# digitalclock2.net
KiCad netlist of a schematic drawn in EAGLE
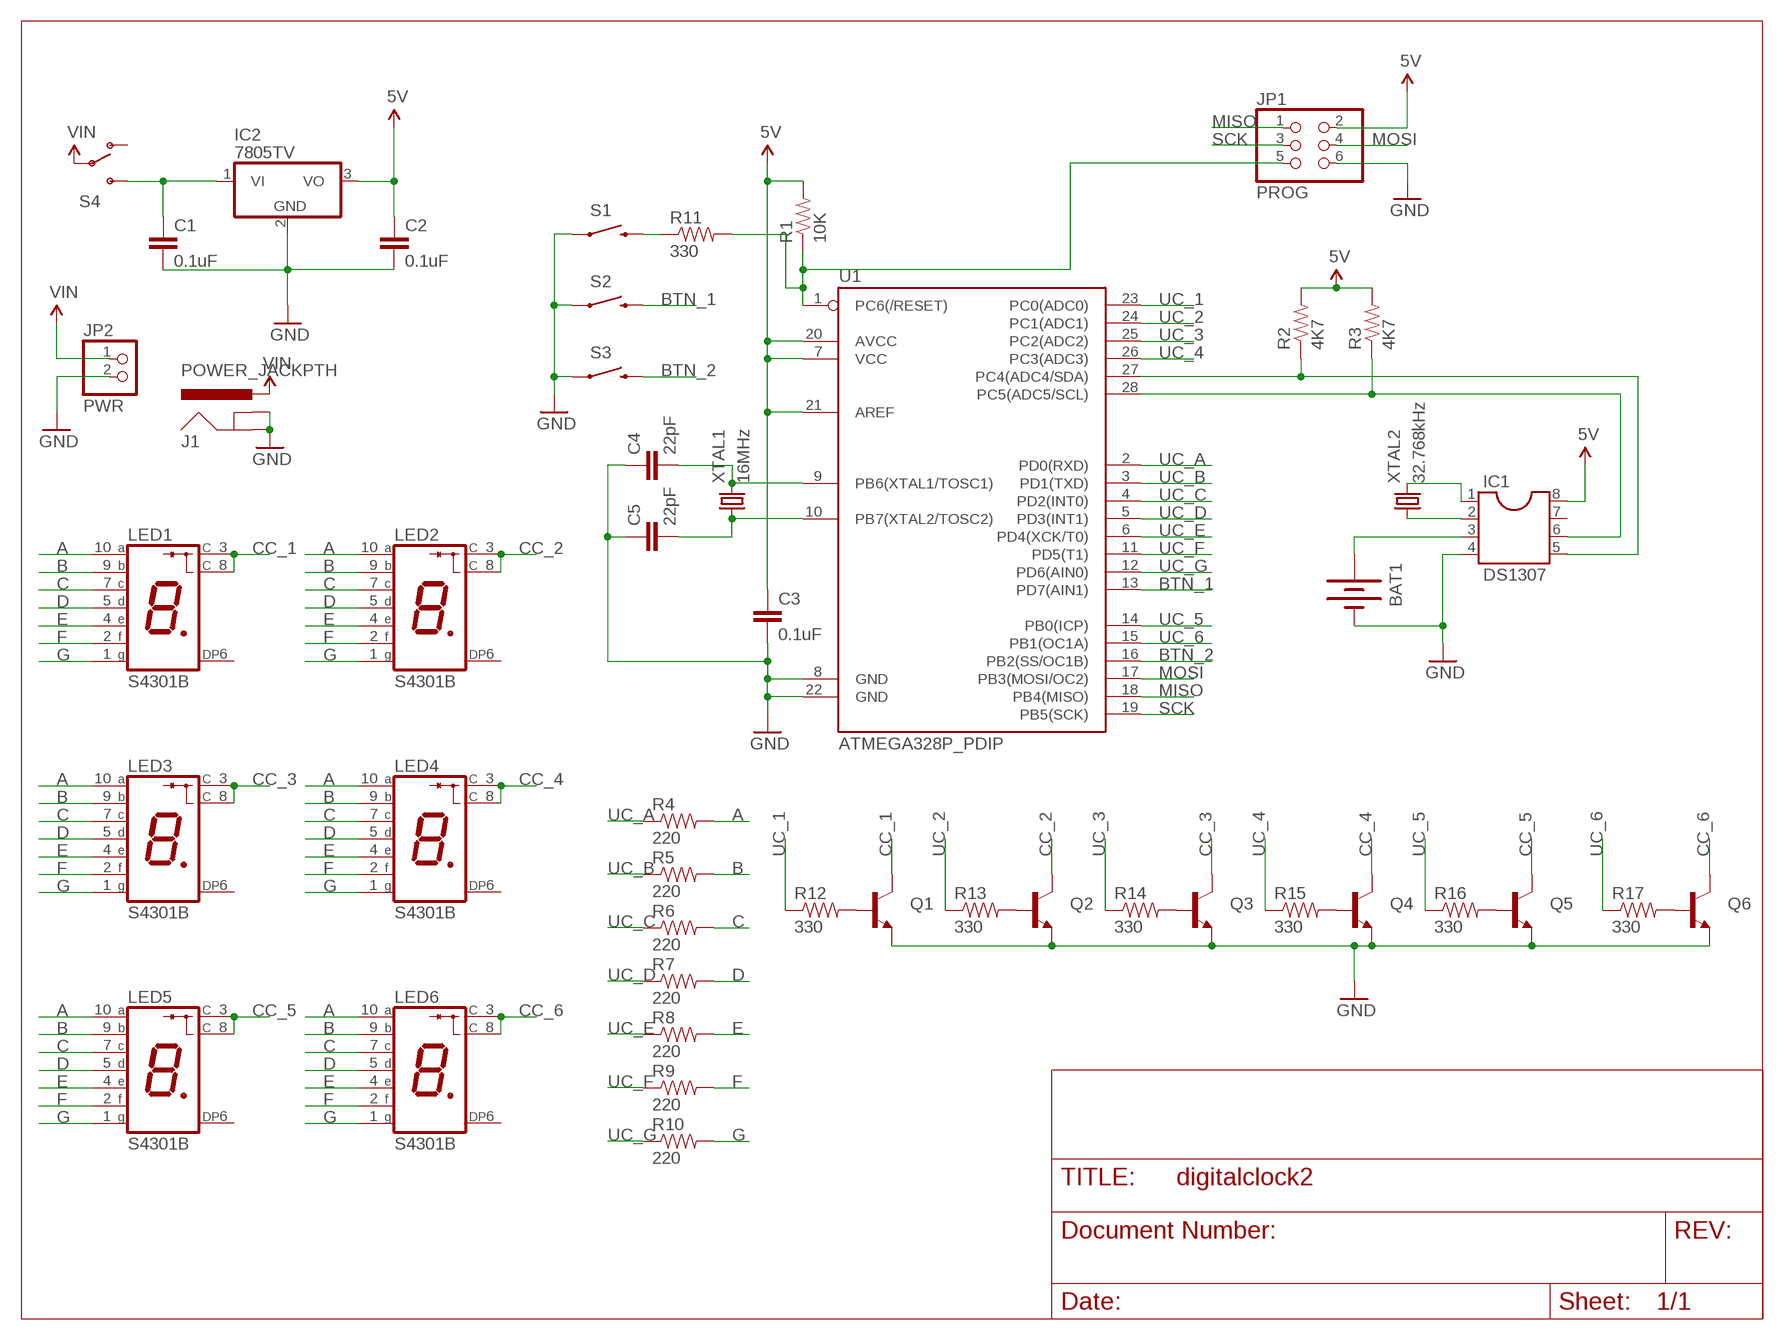
[diagram p0: schematic, sheet 1]

(export (version "E")
  (design (tool "Eeschema 10.0.6"))
  (components
    (comp (ref "BAT1")
      (value "BATTERY20PTH")
      (footprint "eagle-import:BATTCOM_20MM_PTH")
      (libsource (lib "eagle-import") (part "BATTERY20PTH"))
    )
    (comp (ref "C1")
      (value "0.1uF")
      (footprint "eagle-import:CAP-PTH-SMALL")
      (libsource (lib "eagle-import") (part "CAPPTH"))
    )
    (comp (ref "C2")
      (value "0.1uF")
      (footprint "eagle-import:CAP-PTH-SMALL")
      (libsource (lib "eagle-import") (part "CAPPTH"))
    )
    (comp (ref "C3")
      (value "0.1uF")
      (footprint "eagle-import:CAP-PTH-SMALL")
      (libsource (lib "eagle-import") (part "CAPPTH"))
    )
    (comp (ref "C4")
      (value "22pF")
      (footprint "eagle-import:CAP-PTH-SMALL")
      (libsource (lib "eagle-import") (part "CAPPTH"))
    )
    (comp (ref "C5")
      (value "22pF")
      (footprint "eagle-import:CAP-PTH-SMALL")
      (libsource (lib "eagle-import") (part "CAPPTH"))
    )
    (comp (ref "IC1")
      (value "DS1307")
      (footprint "eagle-import:SOCKET-08")
      (libsource (lib "eagle-import") (part "DIL8S"))
    )
    (comp (ref "IC2")
      (value "7805TV")
      (footprint "eagle-import:TO220V")
      (libsource (lib "eagle-import") (part "78TV05"))
    )
    (comp (ref "J1")
      (value "POWER_JACKPTH")
      (footprint "eagle-import:POWER_JACK_PTH")
      (libsource (lib "eagle-import") (part "POWER_JACKPTH"))
    )
    (comp (ref "JP1")
      (value "PROG")
      (footprint "eagle-import:2X03")
      (libsource (lib "eagle-import") (part "PINHD-2X3"))
    )
    (comp (ref "JP2")
      (value "PWR")
      (footprint "eagle-import:1X02")
      (libsource (lib "eagle-import") (part "PINHD-1X2"))
    )
    (comp (ref "LED1")
      (value "S4301B")
      (footprint "eagle-import:S4301B")
      (libsource (lib "eagle-import") (part "S4301B"))
    )
    (comp (ref "LED2")
      (value "S4301B")
      (footprint "eagle-import:S4301B")
      (libsource (lib "eagle-import") (part "S4301B"))
    )
    (comp (ref "LED3")
      (value "S4301B")
      (footprint "eagle-import:S4301B")
      (libsource (lib "eagle-import") (part "S4301B"))
    )
    (comp (ref "LED4")
      (value "S4301B")
      (footprint "eagle-import:S4301B")
      (libsource (lib "eagle-import") (part "S4301B"))
    )
    (comp (ref "LED5")
      (value "S4301B")
      (footprint "eagle-import:S4301B")
      (libsource (lib "eagle-import") (part "S4301B"))
    )
    (comp (ref "LED6")
      (value "S4301B")
      (footprint "eagle-import:S4301B")
      (libsource (lib "eagle-import") (part "S4301B"))
    )
    (comp (ref "Q1")
      (value "TRANSISTOR_NPNTO-92-AMMO")
      (footprint "eagle-import:TO-92-AMMO")
      (libsource (lib "eagle-import") (part "TRANSISTOR_NPNTO-92-AMMO"))
    )
    (comp (ref "Q2")
      (value "TRANSISTOR_NPNTO-92-AMMO")
      (footprint "eagle-import:TO-92-AMMO")
      (libsource (lib "eagle-import") (part "TRANSISTOR_NPNTO-92-AMMO"))
    )
    (comp (ref "Q3")
      (value "TRANSISTOR_NPNTO-92-AMMO")
      (footprint "eagle-import:TO-92-AMMO")
      (libsource (lib "eagle-import") (part "TRANSISTOR_NPNTO-92-AMMO"))
    )
    (comp (ref "Q4")
      (value "TRANSISTOR_NPNTO-92-AMMO")
      (footprint "eagle-import:TO-92-AMMO")
      (libsource (lib "eagle-import") (part "TRANSISTOR_NPNTO-92-AMMO"))
    )
    (comp (ref "Q5")
      (value "TRANSISTOR_NPNTO-92-AMMO")
      (footprint "eagle-import:TO-92-AMMO")
      (libsource (lib "eagle-import") (part "TRANSISTOR_NPNTO-92-AMMO"))
    )
    (comp (ref "Q6")
      (value "TRANSISTOR_NPNTO-92-AMMO")
      (footprint "eagle-import:TO-92-AMMO")
      (libsource (lib "eagle-import") (part "TRANSISTOR_NPNTO-92-AMMO"))
    )
    (comp (ref "R1")
      (value "10K")
      (footprint "eagle-import:AXIAL-0.3")
      (libsource (lib "eagle-import") (part "RESISTORAXIAL-0.3"))
    )
    (comp (ref "R2")
      (value "4K7")
      (footprint "eagle-import:AXIAL-0.3")
      (libsource (lib "eagle-import") (part "RESISTORAXIAL-0.3"))
    )
    (comp (ref "R3")
      (value "4K7")
      (footprint "eagle-import:AXIAL-0.3")
      (libsource (lib "eagle-import") (part "RESISTORAXIAL-0.3"))
    )
    (comp (ref "R4")
      (value "220")
      (footprint "eagle-import:AXIAL-0.3")
      (libsource (lib "eagle-import") (part "RESISTORAXIAL-0.3"))
    )
    (comp (ref "R5")
      (value "220")
      (footprint "eagle-import:AXIAL-0.3")
      (libsource (lib "eagle-import") (part "RESISTORAXIAL-0.3"))
    )
    (comp (ref "R6")
      (value "220")
      (footprint "eagle-import:AXIAL-0.3")
      (libsource (lib "eagle-import") (part "RESISTORAXIAL-0.3"))
    )
    (comp (ref "R7")
      (value "220")
      (footprint "eagle-import:AXIAL-0.3")
      (libsource (lib "eagle-import") (part "RESISTORAXIAL-0.3"))
    )
    (comp (ref "R8")
      (value "220")
      (footprint "eagle-import:AXIAL-0.3")
      (libsource (lib "eagle-import") (part "RESISTORAXIAL-0.3"))
    )
    (comp (ref "R9")
      (value "220")
      (footprint "eagle-import:AXIAL-0.3")
      (libsource (lib "eagle-import") (part "RESISTORAXIAL-0.3"))
    )
    (comp (ref "R10")
      (value "220")
      (footprint "eagle-import:AXIAL-0.3")
      (libsource (lib "eagle-import") (part "RESISTORAXIAL-0.3"))
    )
    (comp (ref "R11")
      (value "330")
      (footprint "eagle-import:AXIAL-0.3")
      (libsource (lib "eagle-import") (part "RESISTORAXIAL-0.3"))
    )
    (comp (ref "R12")
      (value "330")
      (footprint "eagle-import:AXIAL-0.3")
      (libsource (lib "eagle-import") (part "RESISTORAXIAL-0.3"))
    )
    (comp (ref "R13")
      (value "330")
      (footprint "eagle-import:AXIAL-0.3")
      (libsource (lib "eagle-import") (part "RESISTORAXIAL-0.3"))
    )
    (comp (ref "R14")
      (value "330")
      (footprint "eagle-import:AXIAL-0.3")
      (libsource (lib "eagle-import") (part "RESISTORAXIAL-0.3"))
    )
    (comp (ref "R15")
      (value "330")
      (footprint "eagle-import:AXIAL-0.3")
      (libsource (lib "eagle-import") (part "RESISTORAXIAL-0.3"))
    )
    (comp (ref "R16")
      (value "330")
      (footprint "eagle-import:AXIAL-0.3")
      (libsource (lib "eagle-import") (part "RESISTORAXIAL-0.3"))
    )
    (comp (ref "R17")
      (value "330")
      (footprint "eagle-import:AXIAL-0.3")
      (libsource (lib "eagle-import") (part "RESISTORAXIAL-0.3"))
    )
    (comp (ref "S1")
      (value "SWITCH-MOMENTARY-2PTH")
      (footprint "eagle-import:TACTILE-PTH")
      (libsource (lib "eagle-import") (part "SWITCH-MOMENTARY-2PTH"))
    )
    (comp (ref "S2")
      (value "SWITCH-MOMENTARY-2PTH")
      (footprint "eagle-import:TACTILE-PTH")
      (libsource (lib "eagle-import") (part "SWITCH-MOMENTARY-2PTH"))
    )
    (comp (ref "S3")
      (value "SWITCH-MOMENTARY-2PTH")
      (footprint "eagle-import:TACTILE-PTH")
      (libsource (lib "eagle-import") (part "SWITCH-MOMENTARY-2PTH"))
    )
    (comp (ref "S4")
      (value "SWITCH-SPDTPTH")
      (footprint "eagle-import:SWITCH-SPDT")
      (libsource (lib "eagle-import") (part "SWITCH-SPDTPTH"))
    )
    (comp (ref "U1")
      (value "ATMEGA328P_PDIP")
      (footprint "eagle-import:DIL28-3")
      (libsource (lib "eagle-import") (part "ATMEGA328P_PDIP"))
    )
    (comp (ref "XTAL1")
      (value "16MHz")
      (footprint "eagle-import:HC49_S")
      (libsource (lib "eagle-import") (part "CRYSTALHC49S"))
    )
    (comp (ref "XTAL2")
      (value "32.768kHz")
      (footprint "eagle-import:TC26V")
      (libsource (lib "eagle-import") (part "CRYSTALTC26V"))
    )
  )
  (nets
    (net (code "1") (name "/A") (class "Default")
      (node (ref "LED1") (pin "10") (pinfunction "A_10") (pintype "passive"))
      (node (ref "LED2") (pin "10") (pinfunction "A_10") (pintype "passive"))
      (node (ref "LED3") (pin "10") (pinfunction "A_10") (pintype "passive"))
      (node (ref "LED4") (pin "10") (pinfunction "A_10") (pintype "passive"))
      (node (ref "LED5") (pin "10") (pinfunction "A_10") (pintype "passive"))
      (node (ref "LED6") (pin "10") (pinfunction "A_10") (pintype "passive"))
      (node (ref "R4") (pin "P$2") (pinfunction "2_P$2") (pintype "passive"))
    )
    (net (code "2") (name "/B") (class "Default")
      (node (ref "LED1") (pin "9") (pinfunction "B_9") (pintype "passive"))
      (node (ref "LED2") (pin "9") (pinfunction "B_9") (pintype "passive"))
      (node (ref "LED3") (pin "9") (pinfunction "B_9") (pintype "passive"))
      (node (ref "LED4") (pin "9") (pinfunction "B_9") (pintype "passive"))
      (node (ref "LED5") (pin "9") (pinfunction "B_9") (pintype "passive"))
      (node (ref "LED6") (pin "9") (pinfunction "B_9") (pintype "passive"))
      (node (ref "R5") (pin "P$2") (pinfunction "2_P$2") (pintype "passive"))
    )
    (net (code "3") (name "/BTN_1") (class "Default")
      (node (ref "S2") (pin "3") (pinfunction "2_3") (pintype "passive"))
      (node (ref "U1") (pin "13") (pinfunction "PD7(AIN1)_13") (pintype "bidirectional"))
    )
    (net (code "4") (name "/BTN_2") (class "Default")
      (node (ref "S3") (pin "3") (pinfunction "2_3") (pintype "passive"))
      (node (ref "U1") (pin "16") (pinfunction "PB2(SS/OC1B)_16") (pintype "bidirectional"))
    )
    (net (code "5") (name "/C") (class "Default")
      (node (ref "LED1") (pin "7") (pinfunction "C_7") (pintype "passive"))
      (node (ref "LED2") (pin "7") (pinfunction "C_7") (pintype "passive"))
      (node (ref "LED3") (pin "7") (pinfunction "C_7") (pintype "passive"))
      (node (ref "LED4") (pin "7") (pinfunction "C_7") (pintype "passive"))
      (node (ref "LED5") (pin "7") (pinfunction "C_7") (pintype "passive"))
      (node (ref "LED6") (pin "7") (pinfunction "C_7") (pintype "passive"))
      (node (ref "R6") (pin "P$2") (pinfunction "2_P$2") (pintype "passive"))
    )
    (net (code "6") (name "/CC_1") (class "Default")
      (node (ref "LED1") (pin "3") (pinfunction "C_3") (pintype "passive"))
      (node (ref "LED1") (pin "8") (pinfunction "C_8") (pintype "passive"))
      (node (ref "Q1") (pin "3") (pinfunction "C_3") (pintype "passive"))
    )
    (net (code "7") (name "/CC_2") (class "Default")
      (node (ref "LED2") (pin "3") (pinfunction "C_3") (pintype "passive"))
      (node (ref "LED2") (pin "8") (pinfunction "C_8") (pintype "passive"))
      (node (ref "Q2") (pin "3") (pinfunction "C_3") (pintype "passive"))
    )
    (net (code "8") (name "/CC_3") (class "Default")
      (node (ref "LED3") (pin "3") (pinfunction "C_3") (pintype "passive"))
      (node (ref "LED3") (pin "8") (pinfunction "C_8") (pintype "passive"))
      (node (ref "Q3") (pin "3") (pinfunction "C_3") (pintype "passive"))
    )
    (net (code "9") (name "/CC_4") (class "Default")
      (node (ref "LED4") (pin "3") (pinfunction "C_3") (pintype "passive"))
      (node (ref "LED4") (pin "8") (pinfunction "C_8") (pintype "passive"))
      (node (ref "Q4") (pin "3") (pinfunction "C_3") (pintype "passive"))
    )
    (net (code "10") (name "/CC_5") (class "Default")
      (node (ref "LED5") (pin "3") (pinfunction "C_3") (pintype "passive"))
      (node (ref "LED5") (pin "8") (pinfunction "C_8") (pintype "passive"))
      (node (ref "Q5") (pin "3") (pinfunction "C_3") (pintype "passive"))
    )
    (net (code "11") (name "/CC_6") (class "Default")
      (node (ref "LED6") (pin "3") (pinfunction "C_3") (pintype "passive"))
      (node (ref "LED6") (pin "8") (pinfunction "C_8") (pintype "passive"))
      (node (ref "Q6") (pin "3") (pinfunction "C_3") (pintype "passive"))
    )
    (net (code "12") (name "/D") (class "Default")
      (node (ref "LED1") (pin "5") (pinfunction "D_5") (pintype "passive"))
      (node (ref "LED2") (pin "5") (pinfunction "D_5") (pintype "passive"))
      (node (ref "LED3") (pin "5") (pinfunction "D_5") (pintype "passive"))
      (node (ref "LED4") (pin "5") (pinfunction "D_5") (pintype "passive"))
      (node (ref "LED5") (pin "5") (pinfunction "D_5") (pintype "passive"))
      (node (ref "LED6") (pin "5") (pinfunction "D_5") (pintype "passive"))
      (node (ref "R7") (pin "P$2") (pinfunction "2_P$2") (pintype "passive"))
    )
    (net (code "13") (name "/E") (class "Default")
      (node (ref "LED1") (pin "4") (pinfunction "E_4") (pintype "passive"))
      (node (ref "LED2") (pin "4") (pinfunction "E_4") (pintype "passive"))
      (node (ref "LED3") (pin "4") (pinfunction "E_4") (pintype "passive"))
      (node (ref "LED4") (pin "4") (pinfunction "E_4") (pintype "passive"))
      (node (ref "LED5") (pin "4") (pinfunction "E_4") (pintype "passive"))
      (node (ref "LED6") (pin "4") (pinfunction "E_4") (pintype "passive"))
      (node (ref "R8") (pin "P$2") (pinfunction "2_P$2") (pintype "passive"))
    )
    (net (code "14") (name "/F") (class "Default")
      (node (ref "LED1") (pin "2") (pinfunction "F_2") (pintype "passive"))
      (node (ref "LED2") (pin "2") (pinfunction "F_2") (pintype "passive"))
      (node (ref "LED3") (pin "2") (pinfunction "F_2") (pintype "passive"))
      (node (ref "LED4") (pin "2") (pinfunction "F_2") (pintype "passive"))
      (node (ref "LED5") (pin "2") (pinfunction "F_2") (pintype "passive"))
      (node (ref "LED6") (pin "2") (pinfunction "F_2") (pintype "passive"))
      (node (ref "R9") (pin "P$2") (pinfunction "2_P$2") (pintype "passive"))
    )
    (net (code "15") (name "/G") (class "Default")
      (node (ref "LED1") (pin "1") (pinfunction "G_1") (pintype "passive"))
      (node (ref "LED2") (pin "1") (pinfunction "G_1") (pintype "passive"))
      (node (ref "LED3") (pin "1") (pinfunction "G_1") (pintype "passive"))
      (node (ref "LED4") (pin "1") (pinfunction "G_1") (pintype "passive"))
      (node (ref "LED5") (pin "1") (pinfunction "G_1") (pintype "passive"))
      (node (ref "LED6") (pin "1") (pinfunction "G_1") (pintype "passive"))
      (node (ref "R10") (pin "P$2") (pinfunction "2_P$2") (pintype "passive"))
    )
    (net (code "16") (name "/MISO") (class "Default")
      (node (ref "JP1") (pin "1") (pinfunction "1_1") (pintype "passive"))
      (node (ref "U1") (pin "18") (pinfunction "PB4(MISO)_18") (pintype "bidirectional"))
    )
    (net (code "17") (name "/MOSI") (class "Default")
      (node (ref "JP1") (pin "4") (pinfunction "4_4") (pintype "passive"))
      (node (ref "U1") (pin "17") (pinfunction "PB3(MOSI/OC2)_17") (pintype "bidirectional"))
    )
    (net (code "18") (name "/SCK") (class "Default")
      (node (ref "JP1") (pin "3") (pinfunction "3_3") (pintype "passive"))
      (node (ref "U1") (pin "19") (pinfunction "PB5(SCK)_19") (pintype "bidirectional"))
    )
    (net (code "19") (name "/UC_1") (class "Default")
      (node (ref "R12") (pin "P$1") (pinfunction "1_P$1") (pintype "passive"))
      (node (ref "U1") (pin "23") (pinfunction "PC0(ADC0)_23") (pintype "bidirectional"))
    )
    (net (code "20") (name "/UC_2") (class "Default")
      (node (ref "R13") (pin "P$1") (pinfunction "1_P$1") (pintype "passive"))
      (node (ref "U1") (pin "24") (pinfunction "PC1(ADC1)_24") (pintype "bidirectional"))
    )
    (net (code "21") (name "/UC_3") (class "Default")
      (node (ref "R14") (pin "P$1") (pinfunction "1_P$1") (pintype "passive"))
      (node (ref "U1") (pin "25") (pinfunction "PC2(ADC2)_25") (pintype "bidirectional"))
    )
    (net (code "22") (name "/UC_4") (class "Default")
      (node (ref "R15") (pin "P$1") (pinfunction "1_P$1") (pintype "passive"))
      (node (ref "U1") (pin "26") (pinfunction "PC3(ADC3)_26") (pintype "bidirectional"))
    )
    (net (code "23") (name "/UC_5") (class "Default")
      (node (ref "R16") (pin "P$1") (pinfunction "1_P$1") (pintype "passive"))
      (node (ref "U1") (pin "14") (pinfunction "PB0(ICP)_14") (pintype "bidirectional"))
    )
    (net (code "24") (name "/UC_6") (class "Default")
      (node (ref "R17") (pin "P$1") (pinfunction "1_P$1") (pintype "passive"))
      (node (ref "U1") (pin "15") (pinfunction "PB1(OC1A)_15") (pintype "bidirectional"))
    )
    (net (code "25") (name "/UC_A") (class "Default")
      (node (ref "R4") (pin "P$1") (pinfunction "1_P$1") (pintype "passive"))
      (node (ref "U1") (pin "2") (pinfunction "PD0(RXD)_2") (pintype "bidirectional"))
    )
    (net (code "26") (name "/UC_B") (class "Default")
      (node (ref "R5") (pin "P$1") (pinfunction "1_P$1") (pintype "passive"))
      (node (ref "U1") (pin "3") (pinfunction "PD1(TXD)_3") (pintype "bidirectional"))
    )
    (net (code "27") (name "/UC_C") (class "Default")
      (node (ref "R6") (pin "P$1") (pinfunction "1_P$1") (pintype "passive"))
      (node (ref "U1") (pin "4") (pinfunction "PD2(INT0)_4") (pintype "bidirectional"))
    )
    (net (code "28") (name "/UC_D") (class "Default")
      (node (ref "R7") (pin "P$1") (pinfunction "1_P$1") (pintype "passive"))
      (node (ref "U1") (pin "5") (pinfunction "PD3(INT1)_5") (pintype "bidirectional"))
    )
    (net (code "29") (name "/UC_E") (class "Default")
      (node (ref "R8") (pin "P$1") (pinfunction "1_P$1") (pintype "passive"))
      (node (ref "U1") (pin "6") (pinfunction "PD4(XCK/T0)_6") (pintype "bidirectional"))
    )
    (net (code "30") (name "/UC_F") (class "Default")
      (node (ref "R9") (pin "P$1") (pinfunction "1_P$1") (pintype "passive"))
      (node (ref "U1") (pin "11") (pinfunction "PD5(T1)_11") (pintype "bidirectional"))
    )
    (net (code "31") (name "/UC_G") (class "Default")
      (node (ref "R10") (pin "P$1") (pinfunction "1_P$1") (pintype "passive"))
      (node (ref "U1") (pin "12") (pinfunction "PD6(AIN0)_12") (pintype "bidirectional"))
    )
    (net (code "32") (name "5V") (class "Default")
      (node (ref "C2") (pin "1") (pinfunction "1_1") (pintype "passive"))
      (node (ref "C3") (pin "1") (pinfunction "1_1") (pintype "passive"))
      (node (ref "IC1") (pin "8") (pinfunction "8_8") (pintype "passive"))
      (node (ref "IC2") (pin "3") (pinfunction "VO_3") (pintype "passive"))
      (node (ref "JP1") (pin "2") (pinfunction "2_2") (pintype "passive"))
      (node (ref "R1") (pin "P$2") (pinfunction "2_P$2") (pintype "passive"))
      (node (ref "R2") (pin "P$2") (pinfunction "2_P$2") (pintype "passive"))
      (node (ref "R3") (pin "P$2") (pinfunction "2_P$2") (pintype "passive"))
      (node (ref "U1") (pin "20") (pinfunction "AVCC_20") (pintype "bidirectional"))
      (node (ref "U1") (pin "21") (pinfunction "AREF_21") (pintype "bidirectional"))
      (node (ref "U1") (pin "7") (pinfunction "VCC_7") (pintype "bidirectional"))
    )
    (net (code "33") (name "GND") (class "Default")
      (node (ref "BAT1") (pin "2") (pinfunction "-_2") (pintype "power_in"))
      (node (ref "C1") (pin "2") (pinfunction "2_2") (pintype "passive"))
      (node (ref "C2") (pin "2") (pinfunction "2_2") (pintype "passive"))
      (node (ref "C3") (pin "2") (pinfunction "2_2") (pintype "passive"))
      (node (ref "C4") (pin "1") (pinfunction "1_1") (pintype "passive"))
      (node (ref "C5") (pin "1") (pinfunction "1_1") (pintype "passive"))
      (node (ref "IC1") (pin "4") (pinfunction "4_4") (pintype "passive"))
      (node (ref "IC2") (pin "2") (pinfunction "GND_2") (pintype "passive"))
      (node (ref "J1") (pin "GND") (pinfunction "GND_GND") (pintype "bidirectional"))
      (node (ref "J1") (pin "GNDBREAK") (pinfunction "GNDBREAK_GNDBREAK") (pintype "bidirectional"))
      (node (ref "JP1") (pin "6") (pinfunction "6_6") (pintype "passive"))
      (node (ref "JP2") (pin "2") (pinfunction "2_2") (pintype "passive"))
      (node (ref "Q1") (pin "1") (pinfunction "E_1") (pintype "passive"))
      (node (ref "Q2") (pin "1") (pinfunction "E_1") (pintype "passive"))
      (node (ref "Q3") (pin "1") (pinfunction "E_1") (pintype "passive"))
      (node (ref "Q4") (pin "1") (pinfunction "E_1") (pintype "passive"))
      (node (ref "Q5") (pin "1") (pinfunction "E_1") (pintype "passive"))
      (node (ref "Q6") (pin "1") (pinfunction "E_1") (pintype "passive"))
      (node (ref "S1") (pin "1") (pinfunction "1_1") (pintype "passive"))
      (node (ref "S2") (pin "1") (pinfunction "1_1") (pintype "passive"))
      (node (ref "S3") (pin "1") (pinfunction "1_1") (pintype "passive"))
      (node (ref "U1") (pin "22") (pinfunction "GND_22") (pintype "bidirectional"))
      (node (ref "U1") (pin "8") (pinfunction "GND_8") (pintype "bidirectional"))
    )
    (net (code "34") (name "Net-(BAT1-+)") (class "Default")
      (node (ref "BAT1") (pin "1") (pinfunction "+_1") (pintype "power_in"))
      (node (ref "IC1") (pin "3") (pinfunction "3_3") (pintype "passive"))
    )
    (net (code "35") (name "Net-(IC1-Pad1)") (class "Default")
      (node (ref "IC1") (pin "1") (pinfunction "1_1") (pintype "passive"))
      (node (ref "XTAL2") (pin "2") (pinfunction "2_2") (pintype "passive"))
    )
    (net (code "36") (name "Net-(IC1-Pad2)") (class "Default")
      (node (ref "IC1") (pin "2") (pinfunction "2_2") (pintype "passive"))
      (node (ref "XTAL2") (pin "1") (pinfunction "1_1") (pintype "passive"))
    )
    (net (code "37") (name "Net-(IC2-VI)") (class "Default")
      (node (ref "C1") (pin "1") (pinfunction "1_1") (pintype "passive"))
      (node (ref "IC2") (pin "1") (pinfunction "VI_1") (pintype "input"))
      (node (ref "S4") (pin "3") (pinfunction "S_3") (pintype "passive"))
    )
    (net (code "38") (name "Net-(Q1-B)") (class "Default")
      (node (ref "Q1") (pin "2") (pinfunction "B_2") (pintype "passive"))
      (node (ref "R12") (pin "P$2") (pinfunction "2_P$2") (pintype "passive"))
    )
    (net (code "39") (name "Net-(Q2-B)") (class "Default")
      (node (ref "Q2") (pin "2") (pinfunction "B_2") (pintype "passive"))
      (node (ref "R13") (pin "P$2") (pinfunction "2_P$2") (pintype "passive"))
    )
    (net (code "40") (name "Net-(Q3-B)") (class "Default")
      (node (ref "Q3") (pin "2") (pinfunction "B_2") (pintype "passive"))
      (node (ref "R14") (pin "P$2") (pinfunction "2_P$2") (pintype "passive"))
    )
    (net (code "41") (name "Net-(Q4-B)") (class "Default")
      (node (ref "Q4") (pin "2") (pinfunction "B_2") (pintype "passive"))
      (node (ref "R15") (pin "P$2") (pinfunction "2_P$2") (pintype "passive"))
    )
    (net (code "42") (name "Net-(Q5-B)") (class "Default")
      (node (ref "Q5") (pin "2") (pinfunction "B_2") (pintype "passive"))
      (node (ref "R16") (pin "P$2") (pinfunction "2_P$2") (pintype "passive"))
    )
    (net (code "43") (name "Net-(Q6-B)") (class "Default")
      (node (ref "Q6") (pin "2") (pinfunction "B_2") (pintype "passive"))
      (node (ref "R17") (pin "P$2") (pinfunction "2_P$2") (pintype "passive"))
    )
    (net (code "44") (name "Net-(R1-1)") (class "Default")
      (node (ref "JP1") (pin "5") (pinfunction "5_5") (pintype "passive"))
      (node (ref "R1") (pin "P$1") (pinfunction "1_P$1") (pintype "passive"))
      (node (ref "R11") (pin "P$2") (pinfunction "2_P$2") (pintype "passive"))
      (node (ref "U1") (pin "1") (pinfunction "PC6(/RESET)_1") (pintype "bidirectional"))
    )
    (net (code "45") (name "Net-(R2-1)") (class "Default")
      (node (ref "IC1") (pin "5") (pinfunction "5_5") (pintype "passive"))
      (node (ref "R2") (pin "P$1") (pinfunction "1_P$1") (pintype "passive"))
      (node (ref "U1") (pin "27") (pinfunction "PC4(ADC4/SDA)_27") (pintype "bidirectional"))
    )
    (net (code "46") (name "Net-(R3-1)") (class "Default")
      (node (ref "IC1") (pin "6") (pinfunction "6_6") (pintype "passive"))
      (node (ref "R3") (pin "P$1") (pinfunction "1_P$1") (pintype "passive"))
      (node (ref "U1") (pin "28") (pinfunction "PC5(ADC5/SCL)_28") (pintype "bidirectional"))
    )
    (net (code "47") (name "Net-(R11-1)") (class "Default")
      (node (ref "R11") (pin "P$1") (pinfunction "1_P$1") (pintype "passive"))
      (node (ref "S1") (pin "3") (pinfunction "2_3") (pintype "passive"))
    )
    (net (code "48") (name "Net-(U1-PB6(XTAL1{slash}TOSC1))") (class "Default")
      (node (ref "C4") (pin "2") (pinfunction "2_2") (pintype "passive"))
      (node (ref "U1") (pin "9") (pinfunction "PB6(XTAL1/TOSC1)_9") (pintype "bidirectional"))
      (node (ref "XTAL1") (pin "2") (pinfunction "2_2") (pintype "passive"))
    )
    (net (code "49") (name "Net-(U1-PB7(XTAL2{slash}TOSC2))") (class "Default")
      (node (ref "C5") (pin "2") (pinfunction "2_2") (pintype "passive"))
      (node (ref "U1") (pin "10") (pinfunction "PB7(XTAL2/TOSC2)_10") (pintype "bidirectional"))
      (node (ref "XTAL1") (pin "1") (pinfunction "1_1") (pintype "passive"))
    )
    (net (code "50") (name "VIN") (class "Default")
      (node (ref "J1") (pin "PWR") (pinfunction "PWR_PWR") (pintype "bidirectional"))
      (node (ref "JP2") (pin "1") (pinfunction "1_1") (pintype "passive"))
      (node (ref "S4") (pin "2") (pinfunction "P_2") (pintype "passive"))
    )
    (net (code "51") (name "unconnected-(IC1-Pad7)") (class "Default")
      (node (ref "IC1") (pin "7") (pinfunction "7_7") (pintype "passive"))
    )
    (net (code "52") (name "unconnected-(LED1-DP-Pad6)") (class "Default")
      (node (ref "LED1") (pin "6") (pinfunction "DP_6") (pintype "passive"))
    )
    (net (code "53") (name "unconnected-(LED2-DP-Pad6)") (class "Default")
      (node (ref "LED2") (pin "6") (pinfunction "DP_6") (pintype "passive"))
    )
    (net (code "54") (name "unconnected-(LED3-DP-Pad6)") (class "Default")
      (node (ref "LED3") (pin "6") (pinfunction "DP_6") (pintype "passive"))
    )
    (net (code "55") (name "unconnected-(LED4-DP-Pad6)") (class "Default")
      (node (ref "LED4") (pin "6") (pinfunction "DP_6") (pintype "passive"))
    )
    (net (code "56") (name "unconnected-(LED5-DP-Pad6)") (class "Default")
      (node (ref "LED5") (pin "6") (pinfunction "DP_6") (pintype "passive"))
    )
    (net (code "57") (name "unconnected-(LED6-DP-Pad6)") (class "Default")
      (node (ref "LED6") (pin "6") (pinfunction "DP_6") (pintype "passive"))
    )
    (net (code "58") (name "unconnected-(S4-O-Pad1)") (class "Default")
      (node (ref "S4") (pin "1") (pinfunction "O_1") (pintype "passive"))
    )
  )
)
